# Header-PinHeader.net
KiCad netlist of a schematic drawn in Altium Designer
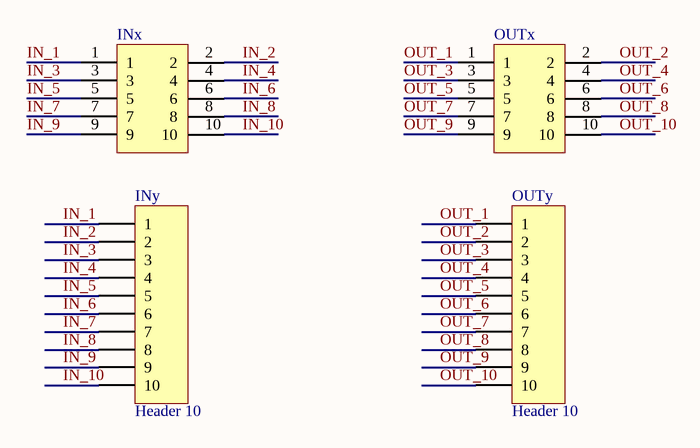
[diagram p0: Header-PinHeader.SchDoc]

(export (version "E")
  (design (tool "Eeschema 10.0.6"))
  (components
    (comp (ref "INx")
      (value "10 pol Header")
      (footprint "10 pol Header")
      (fields (field (name "PUBLISHER") "NONLINEAR LABS"))
      (libsource (lib "10polHeader") (part "10 pol Header"))
    )
    (comp (ref "INy")
      (value "Header 10")
      (footprint "HDR1X10")
      (description "Header, 10-Pin")
      (fields (field (name "PUBLISHER") "Altium Limited"))
      (libsource (lib "Miscellaneous Connectors") (part "Header 10"))
    )
    (comp (ref "OUTx")
      (value "10 pol Header")
      (footprint "10 pol Header")
      (fields (field (name "PUBLISHER") "NONLINEAR LABS"))
      (libsource (lib "10polHeader") (part "10 pol Header"))
    )
    (comp (ref "OUTy")
      (value "Header 10")
      (footprint "HDR1X10")
      (description "Header, 10-Pin")
      (fields (field (name "PUBLISHER") "Altium Limited"))
      (libsource (lib "Miscellaneous Connectors") (part "Header 10"))
    )
  )
  (nets
    (net (code "1") (name "/IN_1") (class "Default")
      (node (ref "INx") (pin "1") (pinfunction "1_1") (pintype "passive"))
      (node (ref "INy") (pin "1") (pinfunction "1_1") (pintype "passive"))
    )
    (net (code "2") (name "/IN_2") (class "Default")
      (node (ref "INx") (pin "2") (pinfunction "2_2") (pintype "passive"))
      (node (ref "INy") (pin "2") (pinfunction "2_2") (pintype "passive"))
    )
    (net (code "3") (name "/IN_3") (class "Default")
      (node (ref "INx") (pin "3") (pinfunction "3_3") (pintype "passive"))
      (node (ref "INy") (pin "3") (pinfunction "3_3") (pintype "passive"))
    )
    (net (code "4") (name "/IN_4") (class "Default")
      (node (ref "INx") (pin "4") (pinfunction "4_4") (pintype "passive"))
      (node (ref "INy") (pin "4") (pinfunction "4_4") (pintype "passive"))
    )
    (net (code "5") (name "/IN_5") (class "Default")
      (node (ref "INx") (pin "5") (pinfunction "5_5") (pintype "passive"))
      (node (ref "INy") (pin "5") (pinfunction "5_5") (pintype "passive"))
    )
    (net (code "6") (name "/IN_6") (class "Default")
      (node (ref "INx") (pin "6") (pinfunction "6_6") (pintype "passive"))
      (node (ref "INy") (pin "6") (pinfunction "6_6") (pintype "passive"))
    )
    (net (code "7") (name "/IN_7") (class "Default")
      (node (ref "INx") (pin "7") (pinfunction "7_7") (pintype "passive"))
      (node (ref "INy") (pin "7") (pinfunction "7_7") (pintype "passive"))
    )
    (net (code "8") (name "/IN_8") (class "Default")
      (node (ref "INx") (pin "8") (pinfunction "8_8") (pintype "passive"))
      (node (ref "INy") (pin "8") (pinfunction "8_8") (pintype "passive"))
    )
    (net (code "9") (name "/IN_9") (class "Default")
      (node (ref "INx") (pin "9") (pinfunction "9_9") (pintype "passive"))
      (node (ref "INy") (pin "9") (pinfunction "9_9") (pintype "passive"))
    )
    (net (code "10") (name "/IN_10") (class "Default")
      (node (ref "INx") (pin "10") (pinfunction "10_10") (pintype "passive"))
      (node (ref "INy") (pin "10") (pinfunction "10_10") (pintype "passive"))
    )
    (net (code "11") (name "/OUT_1") (class "Default")
      (node (ref "OUTx") (pin "1") (pinfunction "1_1") (pintype "passive"))
      (node (ref "OUTy") (pin "1") (pinfunction "1_1") (pintype "passive"))
    )
    (net (code "12") (name "/OUT_2") (class "Default")
      (node (ref "OUTx") (pin "2") (pinfunction "2_2") (pintype "passive"))
      (node (ref "OUTy") (pin "2") (pinfunction "2_2") (pintype "passive"))
    )
    (net (code "13") (name "/OUT_3") (class "Default")
      (node (ref "OUTx") (pin "3") (pinfunction "3_3") (pintype "passive"))
      (node (ref "OUTy") (pin "3") (pinfunction "3_3") (pintype "passive"))
    )
    (net (code "14") (name "/OUT_4") (class "Default")
      (node (ref "OUTx") (pin "4") (pinfunction "4_4") (pintype "passive"))
      (node (ref "OUTy") (pin "4") (pinfunction "4_4") (pintype "passive"))
    )
    (net (code "15") (name "/OUT_5") (class "Default")
      (node (ref "OUTx") (pin "5") (pinfunction "5_5") (pintype "passive"))
      (node (ref "OUTy") (pin "5") (pinfunction "5_5") (pintype "passive"))
    )
    (net (code "16") (name "/OUT_6") (class "Default")
      (node (ref "OUTx") (pin "6") (pinfunction "6_6") (pintype "passive"))
      (node (ref "OUTy") (pin "6") (pinfunction "6_6") (pintype "passive"))
    )
    (net (code "17") (name "/OUT_7") (class "Default")
      (node (ref "OUTx") (pin "7") (pinfunction "7_7") (pintype "passive"))
      (node (ref "OUTy") (pin "7") (pinfunction "7_7") (pintype "passive"))
    )
    (net (code "18") (name "/OUT_8") (class "Default")
      (node (ref "OUTx") (pin "8") (pinfunction "8_8") (pintype "passive"))
      (node (ref "OUTy") (pin "8") (pinfunction "8_8") (pintype "passive"))
    )
    (net (code "19") (name "/OUT_9") (class "Default")
      (node (ref "OUTx") (pin "9") (pinfunction "9_9") (pintype "passive"))
      (node (ref "OUTy") (pin "9") (pinfunction "9_9") (pintype "passive"))
    )
    (net (code "20") (name "/OUT_10") (class "Default")
      (node (ref "OUTx") (pin "10") (pinfunction "10_10") (pintype "passive"))
      (node (ref "OUTy") (pin "10") (pinfunction "10_10") (pintype "passive"))
    )
  )
)
